# External_SIM_Tray.net
KiCad netlist of a schematic drawn in Altium Designer
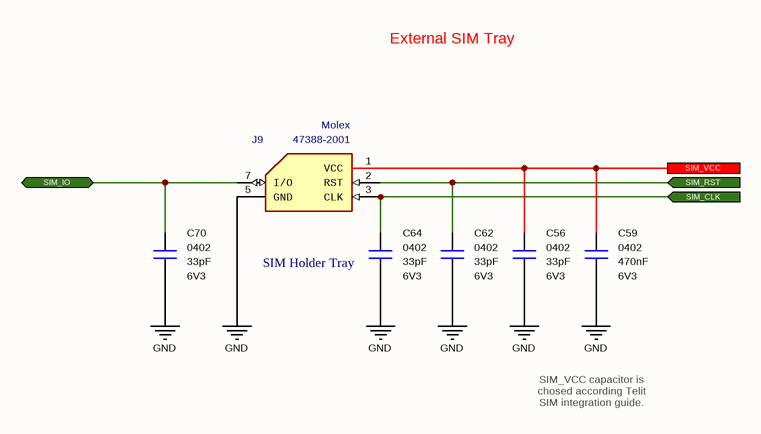
[diagram p0: External SIM Tray.SchDoc]

(export (version "E")
  (design (tool "Eeschema 10.0.6"))
  (components
    (comp (ref "C56")
      (value "33pF")
      (footprint "CAPACITOR_0402")
      (description "Capacitor - 33pF [0402] (Ceramic)")
      (fields
        (field (name "MANUFACTURER PART NUMBER") "C0402C330J9RACAUTO")
        (field (name "MOUSER PART NUMBER") "80-C0402C330J9RAUTO")
        (field (name "CASE") "0402")
        (field (name "VOLTAGE") "6V3")
      )
      (libsource (lib "Ovoo_Library") (part "Capacitor - 33pF [0402-6V3]"))
    )
    (comp (ref "C59")
      (value "470nF")
      (footprint "CAPACITOR_0402")
      (description "Capacitor - 470nF [0402] (Ceramic)")
      (fields
        (field (name "MANUFACTURER PART NUMBER") "04026C474KAT2A")
        (field (name "MOUSER PART NUMBER") "581-04026C474KAT2A")
        (field (name "CASE") "0402")
        (field (name "VOLTAGE") "6V3")
      )
      (libsource (lib "Ovoo_Library") (part "Capacitor - 470nF [0402-6V3]"))
    )
    (comp (ref "C62")
      (value "33pF")
      (footprint "CAPACITOR_0402")
      (description "Capacitor - 33pF [0402] (Ceramic)")
      (fields
        (field (name "MANUFACTURER PART NUMBER") "C0402C330J9RACAUTO")
        (field (name "MOUSER PART NUMBER") "80-C0402C330J9RAUTO")
        (field (name "CASE") "0402")
        (field (name "VOLTAGE") "6V3")
      )
      (libsource (lib "Ovoo_Library") (part "Capacitor - 33pF [0402-6V3]"))
    )
    (comp (ref "C64")
      (value "33pF")
      (footprint "CAPACITOR_0402")
      (description "Capacitor - 33pF [0402] (Ceramic)")
      (fields
        (field (name "MANUFACTURER PART NUMBER") "C0402C330J9RACAUTO")
        (field (name "MOUSER PART NUMBER") "80-C0402C330J9RAUTO")
        (field (name "CASE") "0402")
        (field (name "VOLTAGE") "6V3")
      )
      (libsource (lib "Ovoo_Library") (part "Capacitor - 33pF [0402-6V3]"))
    )
    (comp (ref "C70")
      (value "33pF")
      (footprint "CAPACITOR_0402")
      (description "Capacitor - 33pF [0402] (Ceramic)")
      (fields
        (field (name "MANUFACTURER PART NUMBER") "C0402C330J9RACAUTO")
        (field (name "MOUSER PART NUMBER") "80-C0402C330J9RAUTO")
        (field (name "CASE") "0402")
        (field (name "VOLTAGE") "6V3")
      )
      (libsource (lib "Ovoo_Library") (part "Capacitor - 33pF [0402-6V3]"))
    )
    (comp (ref "J9")
      (value "SIM Holder Tray")
      (footprint "Connector - SIM Tray")
      (description "Memory Card Connectors ASSY 1.90 SIM CARD R IM CARD READER CONN.")
      (fields
        (field (name "MOUSER_PART_NUMBER") "538-47388-2001")
        (field (name "MANUFACTURER_NAME") "Molex")
        (field (name "MANUFACTURER_PART_NUMBER") "47388-2001")
      )
      (libsource (lib "Ovoo_Schematic") (part "Connector - Sim Holder"))
    )
  )
  (nets
    (net (code "1") (name "/SIM_CLK") (class "Default")
      (node (ref "C64") (pin "2") (pinfunction "2_2") (pintype "passive"))
      (node (ref "J9") (pin "3") (pinfunction "CLK_3") (pintype "input"))
    )
    (net (code "2") (name "/SIM_IO") (class "Default")
      (node (ref "C70") (pin "2") (pinfunction "2_2") (pintype "passive"))
      (node (ref "J9") (pin "7") (pinfunction "I/O_7") (pintype "bidirectional"))
    )
    (net (code "3") (name "/SIM_RST") (class "Default")
      (node (ref "C62") (pin "2") (pinfunction "2_2") (pintype "passive"))
      (node (ref "J9") (pin "2") (pinfunction "RST_2") (pintype "input"))
    )
    (net (code "4") (name "/SIM_VCC") (class "Default")
      (node (ref "C56") (pin "2") (pinfunction "2_2") (pintype "passive"))
      (node (ref "C59") (pin "2") (pinfunction "2_2") (pintype "passive"))
      (node (ref "J9") (pin "1") (pinfunction "VCC_1") (pintype "power_in"))
    )
    (net (code "5") (name "GND") (class "Default")
      (node (ref "C56") (pin "1") (pinfunction "1_1") (pintype "passive"))
      (node (ref "C59") (pin "1") (pinfunction "1_1") (pintype "passive"))
      (node (ref "C62") (pin "1") (pinfunction "1_1") (pintype "passive"))
      (node (ref "C64") (pin "1") (pinfunction "1_1") (pintype "passive"))
      (node (ref "C70") (pin "1") (pinfunction "1_1") (pintype "passive"))
      (node (ref "J9") (pin "5") (pinfunction "GND_5") (pintype "power_in"))
    )
  )
)
